# 2021FM_my.net
KiCad netlist of a schematic drawn in Altium Designer
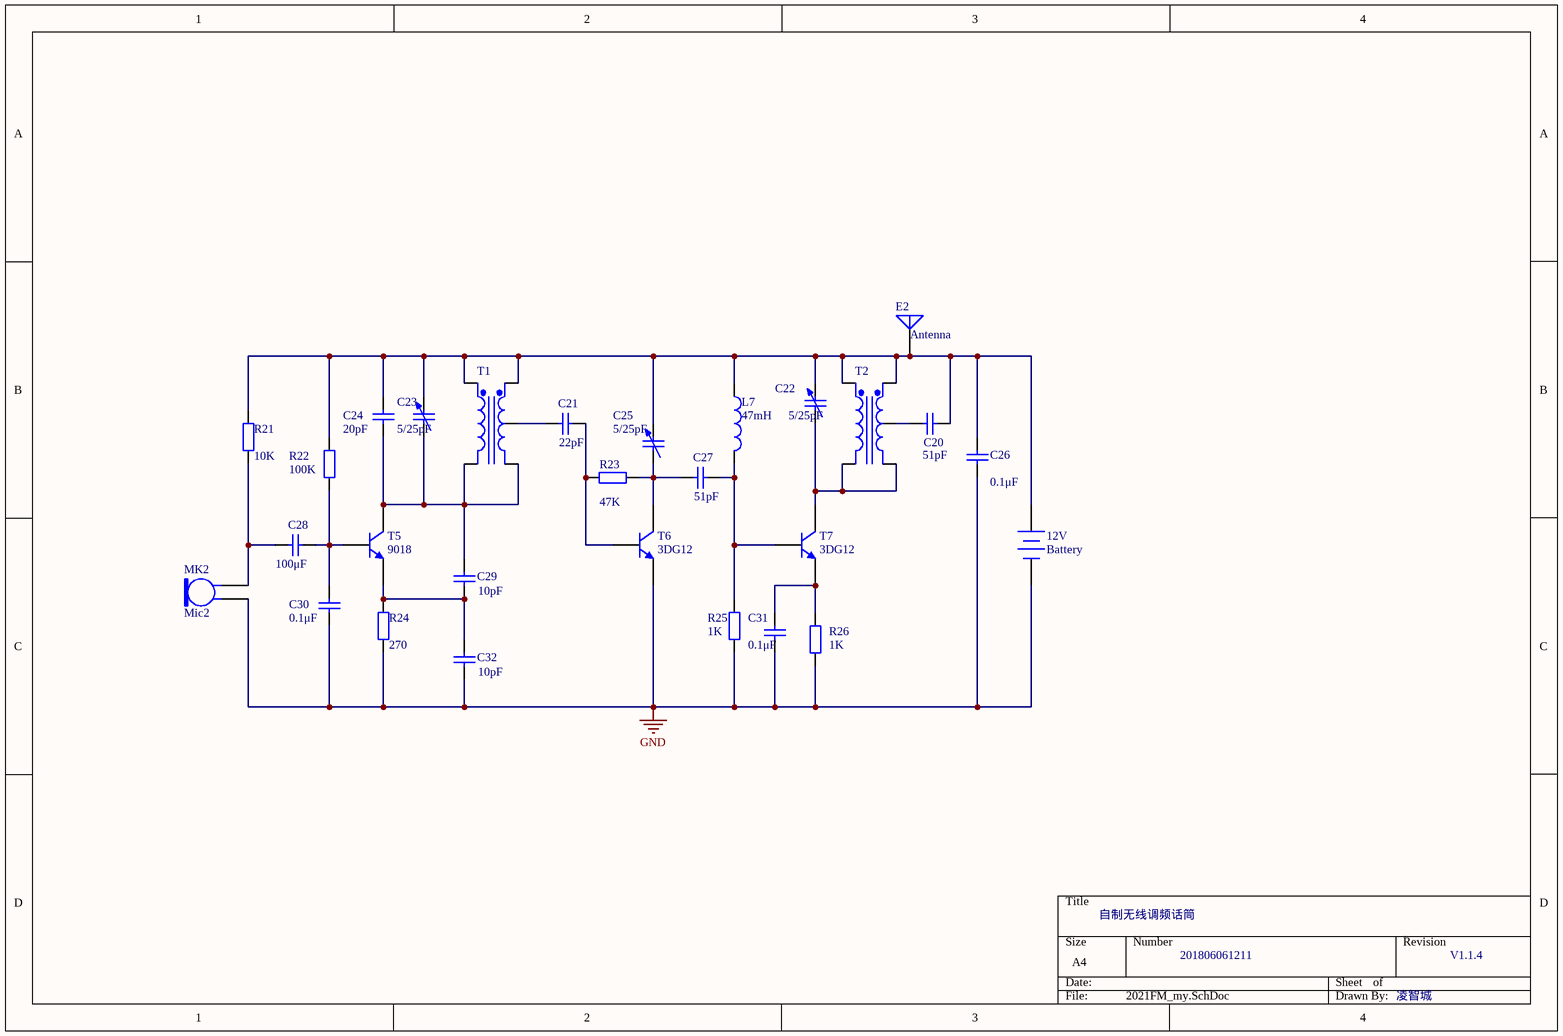
[diagram p0: 2021FM_my.SchDoc]

(export (version "E")
  (design (tool "Eeschema 10.0.6"))
  (components
    (comp (ref "12V")
      (value "Battery")
      (footprint "BAT-2")
      (description "Multicell Battery")
      (fields (field (name "PUBLISHER") "Altium Limited"))
      (libsource (lib "Miscellaneous Devices") (part "Battery"))
    )
    (comp (ref "C20")
      (value "51pF")
      (footprint "RAD-0.3")
      (description "Capacitor")
      (fields (field (name "Comment") "Cap") (field (name "PUBLISHER") "Altium Limited"))
      (libsource (lib "Miscellaneous Devices") (part "Cap"))
    )
    (comp (ref "C21")
      (value "22pF")
      (footprint "RAD-0.3")
      (description "Capacitor")
      (fields (field (name "Comment") "Cap") (field (name "PUBLISHER") "Altium Limited"))
      (libsource (lib "Miscellaneous Devices") (part "Cap"))
    )
    (comp (ref "C22")
      (value "5/25pF")
      (footprint "C1210_N")
      (description "Variable or Adjustable Capacitor")
      (fields (field (name "Comment") "Cap Var") (field (name "PUBLISHER") "Altium Limited"))
      (libsource (lib "Miscellaneous Devices") (part "Cap Var"))
    )
    (comp (ref "C23")
      (value "5/25pF")
      (footprint "C1210_N")
      (description "Variable or Adjustable Capacitor")
      (fields (field (name "Comment") "Cap Var") (field (name "PUBLISHER") "Altium Limited"))
      (libsource (lib "Miscellaneous Devices") (part "Cap Var"))
    )
    (comp (ref "C24")
      (value "20pF")
      (footprint "RAD-0.3")
      (description "Capacitor")
      (fields (field (name "Comment") "Cap") (field (name "PUBLISHER") "Altium Limited"))
      (libsource (lib "Miscellaneous Devices") (part "Cap"))
    )
    (comp (ref "C25")
      (value "5/25pF")
      (footprint "C1210_N")
      (description "Variable or Adjustable Capacitor")
      (fields (field (name "Comment") "Cap Var") (field (name "PUBLISHER") "Altium Limited"))
      (libsource (lib "Miscellaneous Devices") (part "Cap Var"))
    )
    (comp (ref "C26")
      (value "0.1μF")
      (footprint "RAD-0.3")
      (description "Capacitor")
      (fields (field (name "Comment") "Cap") (field (name "PUBLISHER") "Altium Limited"))
      (libsource (lib "Miscellaneous Devices") (part "Cap"))
    )
    (comp (ref "C27")
      (value "51pF")
      (footprint "RAD-0.3")
      (description "Capacitor")
      (fields (field (name "Comment") "Cap") (field (name "PUBLISHER") "Altium Limited"))
      (libsource (lib "Miscellaneous Devices") (part "Cap"))
    )
    (comp (ref "C28")
      (value "100μF")
      (footprint "RAD-0.3")
      (description "Capacitor")
      (fields (field (name "Comment") "Cap") (field (name "PUBLISHER") "Altium Limited"))
      (libsource (lib "Miscellaneous Devices") (part "Cap"))
    )
    (comp (ref "C29")
      (value "10pF")
      (footprint "RAD-0.3")
      (description "Capacitor")
      (fields (field (name "Comment") "Cap") (field (name "PUBLISHER") "Altium Limited"))
      (libsource (lib "Miscellaneous Devices") (part "Cap"))
    )
    (comp (ref "C30")
      (value "0.1μF")
      (footprint "RAD-0.3")
      (description "Capacitor")
      (fields (field (name "Comment") "Cap") (field (name "PUBLISHER") "Altium Limited"))
      (libsource (lib "Miscellaneous Devices") (part "Cap"))
    )
    (comp (ref "C31")
      (value "0.1μF")
      (footprint "RAD-0.3")
      (description "Capacitor")
      (fields (field (name "Comment") "Cap") (field (name "PUBLISHER") "Altium Limited"))
      (libsource (lib "Miscellaneous Devices") (part "Cap"))
    )
    (comp (ref "C32")
      (value "10pF")
      (footprint "RAD-0.3")
      (description "Capacitor")
      (fields (field (name "Comment") "Cap") (field (name "PUBLISHER") "Altium Limited"))
      (libsource (lib "Miscellaneous Devices") (part "Cap"))
    )
    (comp (ref "E2")
      (value "Antenna")
      (footprint "PIN1")
      (description "Generic Antenna")
      (fields (field (name "PUBLISHER") "Altium Limited"))
      (libsource (lib "Miscellaneous Devices") (part "Antenna"))
    )
    (comp (ref "L7")
      (value "47mH")
      (footprint "INDUCTOR")
      (description "Inductor")
      (fields (field (name "PUBLISHER") "Altium Limited"))
      (libsource (lib "Miscellaneous Devices") (part "Inductor"))
    )
    (comp (ref "MK2")
      (value "Mic2")
      (footprint "Microphone")
      (description "Microphone")
      (fields (field (name "PUBLISHER") "Altium Limited"))
      (libsource (lib "Miscellaneous Devices") (part "Mic2"))
    )
    (comp (ref "R21")
      (value "10K")
      (footprint "AXIAL-0.4")
      (description "Resistor")
      (fields (field (name "Comment") "Res2") (field (name "PUBLISHER") "Altium Limited"))
      (libsource (lib "Miscellaneous Devices") (part "Res2"))
    )
    (comp (ref "R22")
      (value "100K")
      (footprint "AXIAL-0.4")
      (description "Resistor")
      (fields (field (name "Comment") "Res2") (field (name "PUBLISHER") "Altium Limited"))
      (libsource (lib "Miscellaneous Devices") (part "Res2"))
    )
    (comp (ref "R23")
      (value "47K")
      (footprint "AXIAL-0.4")
      (description "Resistor")
      (fields (field (name "Comment") "Res2") (field (name "PUBLISHER") "Altium Limited"))
      (libsource (lib "") (part "Res2_1"))
    )
    (comp (ref "R24")
      (value "270")
      (footprint "AXIAL-0.4")
      (description "Resistor")
      (fields (field (name "Comment") "Res2") (field (name "PUBLISHER") "Altium Limited"))
      (libsource (lib "Miscellaneous Devices") (part "Res2"))
    )
    (comp (ref "R25")
      (value "1K")
      (footprint "AXIAL-0.4")
      (description "Resistor")
      (fields (field (name "Comment") "Res2") (field (name "PUBLISHER") "Altium Limited"))
      (libsource (lib "Miscellaneous Devices") (part "Res2"))
    )
    (comp (ref "R26")
      (value "1K")
      (footprint "AXIAL-0.4")
      (description "Resistor")
      (fields (field (name "Comment") "Res2") (field (name "PUBLISHER") "Altium Limited"))
      (libsource (lib "Miscellaneous Devices") (part "Res2"))
    )
    (comp (ref "T1")
      (value "Trans CT Ideal")
      (footprint "TRF_5")
      (description "Center-Tapped Transformer (Ideal)")
      (fields (field (name "PUBLISHER") "Altium Limited"))
      (libsource (lib "Miscellaneous Devices") (part "Trans CT Ideal"))
    )
    (comp (ref "T2")
      (value "Trans CT Ideal")
      (footprint "TRF_5")
      (description "Center-Tapped Transformer (Ideal)")
      (fields (field (name "PUBLISHER") "Altium Limited"))
      (libsource (lib "Miscellaneous Devices") (part "Trans CT Ideal"))
    )
    (comp (ref "T5")
      (value "9018")
      (footprint "three")
      (description "NPN Bipolar Transistor")
      (fields (field (name "PUBLISHER") "Altium Limited"))
      (libsource (lib "Miscellaneous Devices") (part "NPN"))
    )
    (comp (ref "T6")
      (value "3DG12")
      (footprint "three")
      (description "NPN Bipolar Transistor")
      (fields (field (name "PUBLISHER") "Altium Limited"))
      (libsource (lib "Miscellaneous Devices") (part "NPN"))
    )
    (comp (ref "T7")
      (value "3DG12")
      (footprint "three")
      (description "NPN Bipolar Transistor")
      (fields (field (name "PUBLISHER") "Altium Limited"))
      (libsource (lib "Miscellaneous Devices") (part "NPN"))
    )
  )
  (nets
    (net (code "1") (name "GND") (class "Default")
      (node (ref "12V") (pin "2") (pinfunction "-_2") (pintype "passive"))
      (node (ref "C26") (pin "1") (pinfunction "1_1") (pintype "passive"))
      (node (ref "C30") (pin "1") (pinfunction "1_1") (pintype "passive"))
      (node (ref "C31") (pin "1") (pinfunction "1_1") (pintype "passive"))
      (node (ref "C32") (pin "1") (pinfunction "1_1") (pintype "passive"))
      (node (ref "MK2") (pin "1") (pinfunction "1_1") (pintype "passive"))
      (node (ref "R24") (pin "1") (pinfunction "1_1") (pintype "passive"))
      (node (ref "R25") (pin "1") (pinfunction "1_1") (pintype "passive"))
      (node (ref "R26") (pin "1") (pinfunction "1_1") (pintype "passive"))
      (node (ref "T6") (pin "3") (pinfunction "E_3") (pintype "passive"))
    )
    (net (code "2") (name "Net-(12V-+)") (class "Default")
      (node (ref "12V") (pin "1") (pinfunction "+_1") (pintype "passive"))
      (node (ref "C20") (pin "2") (pinfunction "2_2") (pintype "passive"))
      (node (ref "C22") (pin "2") (pinfunction "2_2") (pintype "passive"))
      (node (ref "C23") (pin "2") (pinfunction "2_2") (pintype "passive"))
      (node (ref "C24") (pin "2") (pinfunction "2_2") (pintype "passive"))
      (node (ref "C25") (pin "2") (pinfunction "2_2") (pintype "passive"))
      (node (ref "C26") (pin "2") (pinfunction "2_2") (pintype "passive"))
      (node (ref "E2") (pin "1") (pinfunction "A_1") (pintype "passive"))
      (node (ref "L7") (pin "1") (pinfunction "1_1") (pintype "passive"))
      (node (ref "R21") (pin "2") (pinfunction "2_2") (pintype "passive"))
      (node (ref "R22") (pin "2") (pinfunction "2_2") (pintype "passive"))
      (node (ref "T1") (pin "1") (pinfunction "Pri+_1") (pintype "passive"))
      (node (ref "T1") (pin "3") (pinfunction "Sec+_3") (pintype "passive"))
      (node (ref "T2") (pin "1") (pinfunction "Pri+_1") (pintype "passive"))
      (node (ref "T2") (pin "3") (pinfunction "Sec+_3") (pintype "passive"))
    )
    (net (code "3") (name "Net-(C28-Pad1)") (class "Default")
      (node (ref "C28") (pin "1") (pinfunction "1_1") (pintype "passive"))
      (node (ref "MK2") (pin "2") (pinfunction "2_2") (pintype "passive"))
      (node (ref "R21") (pin "1") (pinfunction "1_1") (pintype "passive"))
    )
    (net (code "4") (name "Net-(T1-Pri-)") (class "Default")
      (node (ref "C23") (pin "1") (pinfunction "1_1") (pintype "passive"))
      (node (ref "C24") (pin "1") (pinfunction "1_1") (pintype "passive"))
      (node (ref "C29") (pin "2") (pinfunction "2_2") (pintype "passive"))
      (node (ref "T1") (pin "2") (pinfunction "Pri-_2") (pintype "passive"))
      (node (ref "T1") (pin "5") (pinfunction "Sec-_5") (pintype "passive"))
      (node (ref "T5") (pin "1") (pinfunction "C_1") (pintype "passive"))
    )
    (net (code "5") (name "Net-(T1-SecCT)") (class "Default")
      (node (ref "C21") (pin "1") (pinfunction "1_1") (pintype "passive"))
      (node (ref "T1") (pin "4") (pinfunction "SecCT_4") (pintype "passive"))
    )
    (net (code "6") (name "Net-(T2-Pri-)") (class "Default")
      (node (ref "C22") (pin "1") (pinfunction "1_1") (pintype "passive"))
      (node (ref "T2") (pin "2") (pinfunction "Pri-_2") (pintype "passive"))
      (node (ref "T2") (pin "5") (pinfunction "Sec-_5") (pintype "passive"))
      (node (ref "T7") (pin "1") (pinfunction "C_1") (pintype "passive"))
    )
    (net (code "7") (name "Net-(T2-SecCT)") (class "Default")
      (node (ref "C20") (pin "1") (pinfunction "1_1") (pintype "passive"))
      (node (ref "T2") (pin "4") (pinfunction "SecCT_4") (pintype "passive"))
    )
    (net (code "8") (name "Net-(T5-B)") (class "Default")
      (node (ref "C28") (pin "2") (pinfunction "2_2") (pintype "passive"))
      (node (ref "C30") (pin "2") (pinfunction "2_2") (pintype "passive"))
      (node (ref "R22") (pin "1") (pinfunction "1_1") (pintype "passive"))
      (node (ref "T5") (pin "2") (pinfunction "B_2") (pintype "passive"))
    )
    (net (code "9") (name "Net-(T5-E)") (class "Default")
      (node (ref "C29") (pin "1") (pinfunction "1_1") (pintype "passive"))
      (node (ref "C32") (pin "2") (pinfunction "2_2") (pintype "passive"))
      (node (ref "R24") (pin "2") (pinfunction "2_2") (pintype "passive"))
      (node (ref "T5") (pin "3") (pinfunction "E_3") (pintype "passive"))
    )
    (net (code "10") (name "Net-(T6-B)") (class "Default")
      (node (ref "C21") (pin "2") (pinfunction "2_2") (pintype "passive"))
      (node (ref "R23") (pin "1") (pinfunction "1_1") (pintype "passive"))
      (node (ref "T6") (pin "2") (pinfunction "B_2") (pintype "passive"))
    )
    (net (code "11") (name "Net-(T6-C)") (class "Default")
      (node (ref "C25") (pin "1") (pinfunction "1_1") (pintype "passive"))
      (node (ref "C27") (pin "1") (pinfunction "1_1") (pintype "passive"))
      (node (ref "R23") (pin "2") (pinfunction "2_2") (pintype "passive"))
      (node (ref "T6") (pin "1") (pinfunction "C_1") (pintype "passive"))
    )
    (net (code "12") (name "Net-(T7-B)") (class "Default")
      (node (ref "C27") (pin "2") (pinfunction "2_2") (pintype "passive"))
      (node (ref "L7") (pin "2") (pinfunction "2_2") (pintype "passive"))
      (node (ref "R25") (pin "2") (pinfunction "2_2") (pintype "passive"))
      (node (ref "T7") (pin "2") (pinfunction "B_2") (pintype "passive"))
    )
    (net (code "13") (name "Net-(T7-E)") (class "Default")
      (node (ref "C31") (pin "2") (pinfunction "2_2") (pintype "passive"))
      (node (ref "R26") (pin "2") (pinfunction "2_2") (pintype "passive"))
      (node (ref "T7") (pin "3") (pinfunction "E_3") (pintype "passive"))
    )
  )
)
